# main.net
KiCad netlist of a schematic drawn in EAGLE
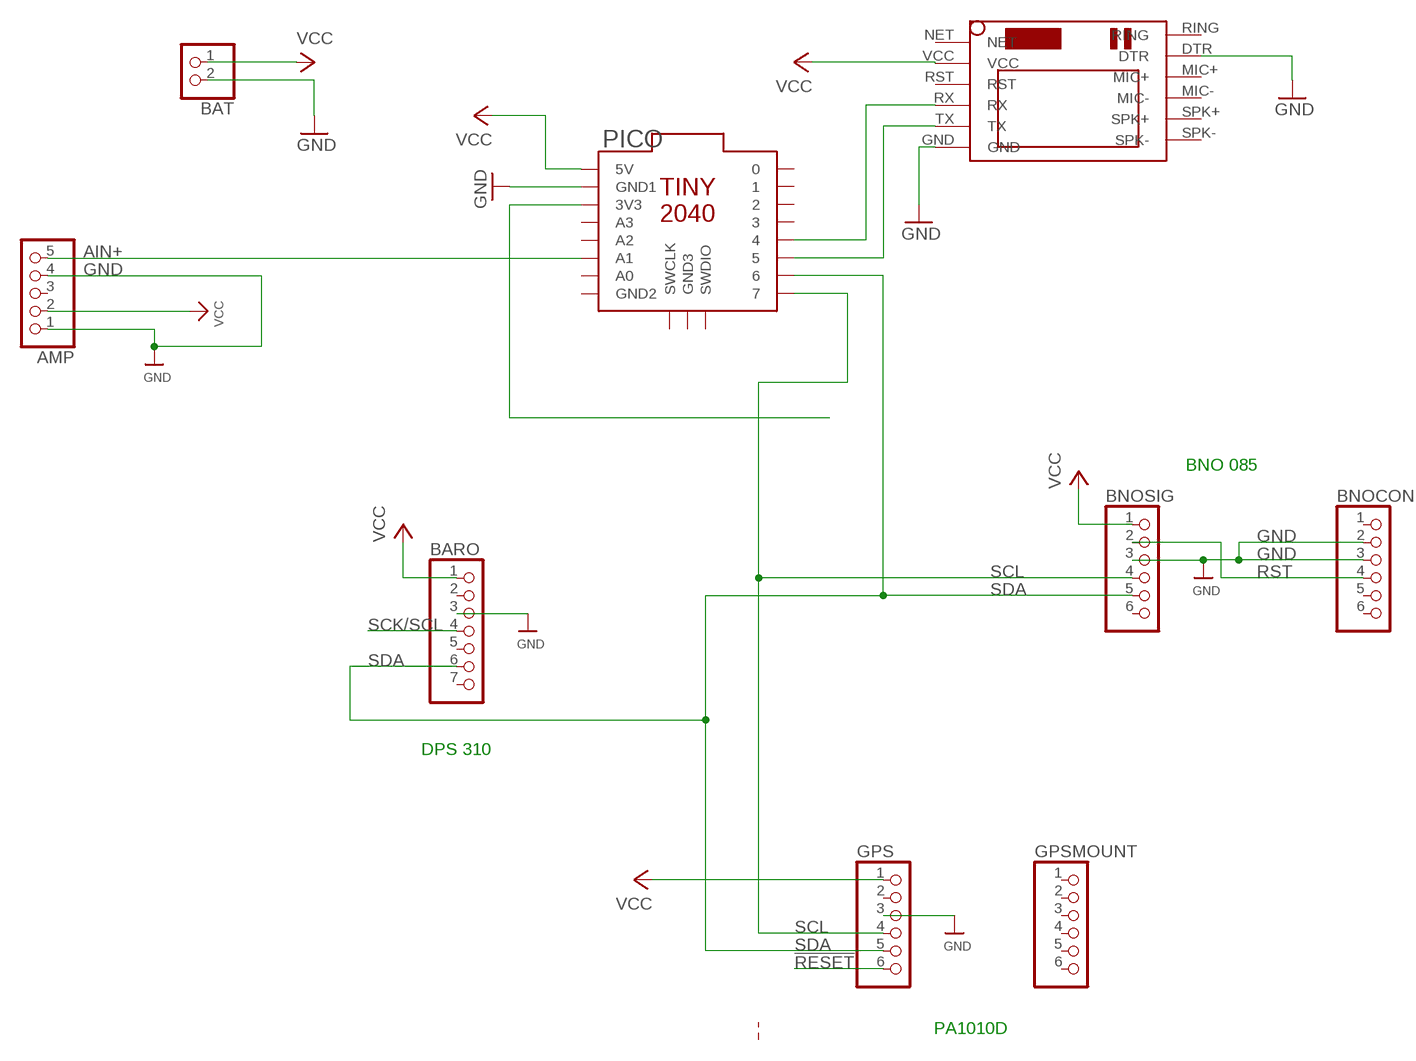
[diagram p0: schematic, sheet 1]

(export (version "E")
  (design (tool "Eeschema 10.0.6"))
  (components
    (comp (ref "AMP")
      (value "HEADER-1X570MIL")
      (footprint "eagle-import:1X05_ROUND_70")
      (libsource (lib "eagle-import") (part "HEADER-1X570MIL"))
    )
    (comp (ref "BARO")
      (value "HEADER-1X770MIL")
      (footprint "eagle-import:1X07_ROUND_70")
      (libsource (lib "eagle-import") (part "HEADER-1X770MIL"))
    )
    (comp (ref "BAT")
      (value "JST_2PIN-THM-RA")
      (footprint "eagle-import:JST-PH-2-THM-RA")
      (libsource (lib "eagle-import") (part "JST_2PIN-THM-RA"))
    )
    (comp (ref "BNOCON")
      (value "HEADER-1X670MIL")
      (footprint "eagle-import:1X06_ROUND_70")
      (libsource (lib "eagle-import") (part "HEADER-1X670MIL"))
    )
    (comp (ref "BNOSIG")
      (value "HEADER-1X670MIL")
      (footprint "eagle-import:1X06_ROUND_70")
      (libsource (lib "eagle-import") (part "HEADER-1X670MIL"))
    )
    (comp (ref "GPS")
      (value "HEADER-1X670MIL")
      (footprint "eagle-import:1X06_ROUND_70")
      (libsource (lib "eagle-import") (part "HEADER-1X670MIL"))
    )
    (comp (ref "GPSMOUNT")
      (value "HEADER-1X670MIL")
      (footprint "eagle-import:1X06_ROUND_70")
      (libsource (lib "eagle-import") (part "HEADER-1X670MIL"))
    )
    (comp (ref "PICO")
      (value "TINY2040")
      (footprint "eagle-import:TINY2040")
      (libsource (lib "eagle-import") (part "TINY2040"))
    )
    (comp (ref "SIM")
      (value "SIM800LMODULE")
      (footprint "eagle-import:SIM800LMODULE")
      (libsource (lib "eagle-import") (part "SIM800LMODULE"))
    )
  )
  (nets
    (net (code "1") (name "/AIN+") (class "Default")
      (node (ref "AMP") (pin "5") (pinfunction "5_5") (pintype "passive"))
      (node (ref "PICO") (pin "A1") (pinfunction "A1_A1") (pintype "bidirectional"))
    )
    (net (code "2") (name "/RST") (class "Default")
      (node (ref "BNOCON") (pin "4") (pinfunction "4_4") (pintype "passive"))
      (node (ref "BNOSIG") (pin "2") (pinfunction "2_2") (pintype "passive"))
    )
    (net (code "3") (name "/SCK{slash}SCL") (class "Default")
      (node (ref "BARO") (pin "4") (pinfunction "4_4") (pintype "passive"))
    )
    (net (code "4") (name "/SCL") (class "Default")
      (node (ref "BNOSIG") (pin "4") (pinfunction "4_4") (pintype "passive"))
      (node (ref "GPS") (pin "4") (pinfunction "4_4") (pintype "passive"))
      (node (ref "PICO") (pin "7") (pinfunction "7_7") (pintype "bidirectional"))
    )
    (net (code "5") (name "/SDA") (class "Default")
      (node (ref "BARO") (pin "6") (pinfunction "6_6") (pintype "passive"))
      (node (ref "BNOSIG") (pin "5") (pinfunction "5_5") (pintype "passive"))
      (node (ref "GPS") (pin "5") (pinfunction "5_5") (pintype "passive"))
      (node (ref "PICO") (pin "6") (pinfunction "6_6") (pintype "bidirectional"))
    )
    (net (code "6") (name "/~{RESET}") (class "Default")
      (node (ref "GPS") (pin "6") (pinfunction "6_6") (pintype "passive"))
    )
    (net (code "7") (name "GND") (class "Default")
      (node (ref "AMP") (pin "1") (pinfunction "1_1") (pintype "passive"))
      (node (ref "AMP") (pin "4") (pinfunction "4_4") (pintype "passive"))
      (node (ref "BARO") (pin "3") (pinfunction "3_3") (pintype "passive"))
      (node (ref "BAT") (pin "2") (pinfunction "1_2") (pintype "passive"))
      (node (ref "BNOCON") (pin "2") (pinfunction "2_2") (pintype "passive"))
      (node (ref "BNOCON") (pin "3") (pinfunction "3_3") (pintype "passive"))
      (node (ref "BNOSIG") (pin "3") (pinfunction "3_3") (pintype "passive"))
      (node (ref "GPS") (pin "3") (pinfunction "3_3") (pintype "passive"))
      (node (ref "PICO") (pin "GND1") (pinfunction "GND1_GND1") (pintype "bidirectional"))
      (node (ref "SIM") (pin "DTR") (pinfunction "DTR_DTR") (pintype "bidirectional"))
      (node (ref "SIM") (pin "GND") (pinfunction "GND_GND") (pintype "bidirectional"))
    )
    (net (code "8") (name "Net-(PICO-Pad4)") (class "Default")
      (node (ref "PICO") (pin "4") (pinfunction "4_4") (pintype "bidirectional"))
      (node (ref "SIM") (pin "RX") (pinfunction "RX_RX") (pintype "bidirectional"))
    )
    (net (code "9") (name "Net-(PICO-Pad5)") (class "Default")
      (node (ref "PICO") (pin "5") (pinfunction "5_5") (pintype "bidirectional"))
      (node (ref "SIM") (pin "TX") (pinfunction "TX_TX") (pintype "bidirectional"))
    )
    (net (code "10") (name "VCC") (class "Default")
      (node (ref "AMP") (pin "2") (pinfunction "2_2") (pintype "passive"))
      (node (ref "BARO") (pin "1") (pinfunction "1_1") (pintype "passive"))
      (node (ref "BAT") (pin "1") (pinfunction "2_1") (pintype "passive"))
      (node (ref "BNOSIG") (pin "1") (pinfunction "1_1") (pintype "passive"))
      (node (ref "GPS") (pin "1") (pinfunction "1_1") (pintype "passive"))
      (node (ref "PICO") (pin "5V") (pinfunction "5V_5V") (pintype "bidirectional"))
      (node (ref "SIM") (pin "VCC") (pinfunction "VCC_VCC") (pintype "bidirectional"))
    )
    (net (code "11") (name "unconnected-(AMP-Pad3)") (class "Default")
      (node (ref "AMP") (pin "3") (pinfunction "3_3") (pintype "passive"))
    )
    (net (code "12") (name "unconnected-(BARO-Pad2)") (class "Default")
      (node (ref "BARO") (pin "2") (pinfunction "2_2") (pintype "passive"))
    )
    (net (code "13") (name "unconnected-(BARO-Pad5)") (class "Default")
      (node (ref "BARO") (pin "5") (pinfunction "5_5") (pintype "passive"))
    )
    (net (code "14") (name "unconnected-(BARO-Pad7)") (class "Default")
      (node (ref "BARO") (pin "7") (pinfunction "7_7") (pintype "passive"))
    )
    (net (code "15") (name "unconnected-(BNOCON-Pad1)") (class "Default")
      (node (ref "BNOCON") (pin "1") (pinfunction "1_1") (pintype "passive"))
    )
    (net (code "16") (name "unconnected-(BNOCON-Pad5)") (class "Default")
      (node (ref "BNOCON") (pin "5") (pinfunction "5_5") (pintype "passive"))
    )
    (net (code "17") (name "unconnected-(BNOCON-Pad6)") (class "Default")
      (node (ref "BNOCON") (pin "6") (pinfunction "6_6") (pintype "passive"))
    )
    (net (code "18") (name "unconnected-(BNOSIG-Pad6)") (class "Default")
      (node (ref "BNOSIG") (pin "6") (pinfunction "6_6") (pintype "passive"))
    )
    (net (code "19") (name "unconnected-(GPS-Pad2)") (class "Default")
      (node (ref "GPS") (pin "2") (pinfunction "2_2") (pintype "passive"))
    )
    (net (code "20") (name "unconnected-(GPSMOUNT-Pad1)") (class "Default")
      (node (ref "GPSMOUNT") (pin "1") (pinfunction "1_1") (pintype "passive"))
    )
    (net (code "21") (name "unconnected-(GPSMOUNT-Pad2)") (class "Default")
      (node (ref "GPSMOUNT") (pin "2") (pinfunction "2_2") (pintype "passive"))
    )
    (net (code "22") (name "unconnected-(GPSMOUNT-Pad3)") (class "Default")
      (node (ref "GPSMOUNT") (pin "3") (pinfunction "3_3") (pintype "passive"))
    )
    (net (code "23") (name "unconnected-(GPSMOUNT-Pad4)") (class "Default")
      (node (ref "GPSMOUNT") (pin "4") (pinfunction "4_4") (pintype "passive"))
    )
    (net (code "24") (name "unconnected-(GPSMOUNT-Pad5)") (class "Default")
      (node (ref "GPSMOUNT") (pin "5") (pinfunction "5_5") (pintype "passive"))
    )
    (net (code "25") (name "unconnected-(GPSMOUNT-Pad6)") (class "Default")
      (node (ref "GPSMOUNT") (pin "6") (pinfunction "6_6") (pintype "passive"))
    )
    (net (code "26") (name "unconnected-(PICO-Pad0)") (class "Default")
      (node (ref "PICO") (pin "0") (pinfunction "0_0") (pintype "bidirectional"))
    )
    (net (code "27") (name "unconnected-(PICO-Pad1)") (class "Default")
      (node (ref "PICO") (pin "1") (pinfunction "1_1") (pintype "bidirectional"))
    )
    (net (code "28") (name "unconnected-(PICO-Pad2)") (class "Default")
      (node (ref "PICO") (pin "2") (pinfunction "2_2") (pintype "bidirectional"))
    )
    (net (code "29") (name "unconnected-(PICO-Pad3)") (class "Default")
      (node (ref "PICO") (pin "3") (pinfunction "3_3") (pintype "bidirectional"))
    )
    (net (code "30") (name "unconnected-(PICO-Pad3V3)") (class "Default")
      (node (ref "PICO") (pin "3V3") (pinfunction "3V3_3V3") (pintype "bidirectional"))
    )
    (net (code "31") (name "unconnected-(PICO-PadA0)") (class "Default")
      (node (ref "PICO") (pin "A0") (pinfunction "A0_A0") (pintype "bidirectional"))
    )
    (net (code "32") (name "unconnected-(PICO-PadA2)") (class "Default")
      (node (ref "PICO") (pin "A2") (pinfunction "A2_A2") (pintype "bidirectional"))
    )
    (net (code "33") (name "unconnected-(PICO-PadA3)") (class "Default")
      (node (ref "PICO") (pin "A3") (pinfunction "A3_A3") (pintype "bidirectional"))
    )
    (net (code "34") (name "unconnected-(PICO-PadGND2)") (class "Default")
      (node (ref "PICO") (pin "GND2") (pinfunction "GND2_GND2") (pintype "bidirectional"))
    )
    (net (code "35") (name "unconnected-(PICO-PadGND3)") (class "Default")
      (node (ref "PICO") (pin "GND3") (pinfunction "GND3_GND3") (pintype "bidirectional"))
    )
    (net (code "36") (name "unconnected-(PICO-PadSWCLK)") (class "Default")
      (node (ref "PICO") (pin "SWCLK") (pinfunction "SWCLK_SWCLK") (pintype "bidirectional"))
    )
    (net (code "37") (name "unconnected-(PICO-PadSWDIO)") (class "Default")
      (node (ref "PICO") (pin "SWDIO") (pinfunction "SWDIO_SWDIO") (pintype "bidirectional"))
    )
    (net (code "38") (name "unconnected-(SIM-PadMIC+)") (class "Default")
      (node (ref "SIM") (pin "MIC+") (pinfunction "MIC+_MIC+") (pintype "bidirectional"))
    )
    (net (code "39") (name "unconnected-(SIM-PadMIC-)") (class "Default")
      (node (ref "SIM") (pin "MIC-") (pinfunction "MIC-_MIC-") (pintype "bidirectional"))
    )
    (net (code "40") (name "unconnected-(SIM-PadNET)") (class "Default")
      (node (ref "SIM") (pin "NET") (pinfunction "NET_NET") (pintype "bidirectional"))
    )
    (net (code "41") (name "unconnected-(SIM-PadRING)") (class "Default")
      (node (ref "SIM") (pin "RING") (pinfunction "RING_RING") (pintype "bidirectional"))
    )
    (net (code "42") (name "unconnected-(SIM-PadRST)") (class "Default")
      (node (ref "SIM") (pin "RST") (pinfunction "RST_RST") (pintype "bidirectional"))
    )
    (net (code "43") (name "unconnected-(SIM-PadSPK+)") (class "Default")
      (node (ref "SIM") (pin "SPK+") (pinfunction "SPK+_SPK+") (pintype "bidirectional"))
    )
    (net (code "44") (name "unconnected-(SIM-PadSPK-)") (class "Default")
      (node (ref "SIM") (pin "SPK-") (pinfunction "SPK-_SPK-") (pintype "bidirectional"))
    )
  )
)
